# transceiver-AX5043.net
KiCad netlist of a schematic drawn in EAGLE
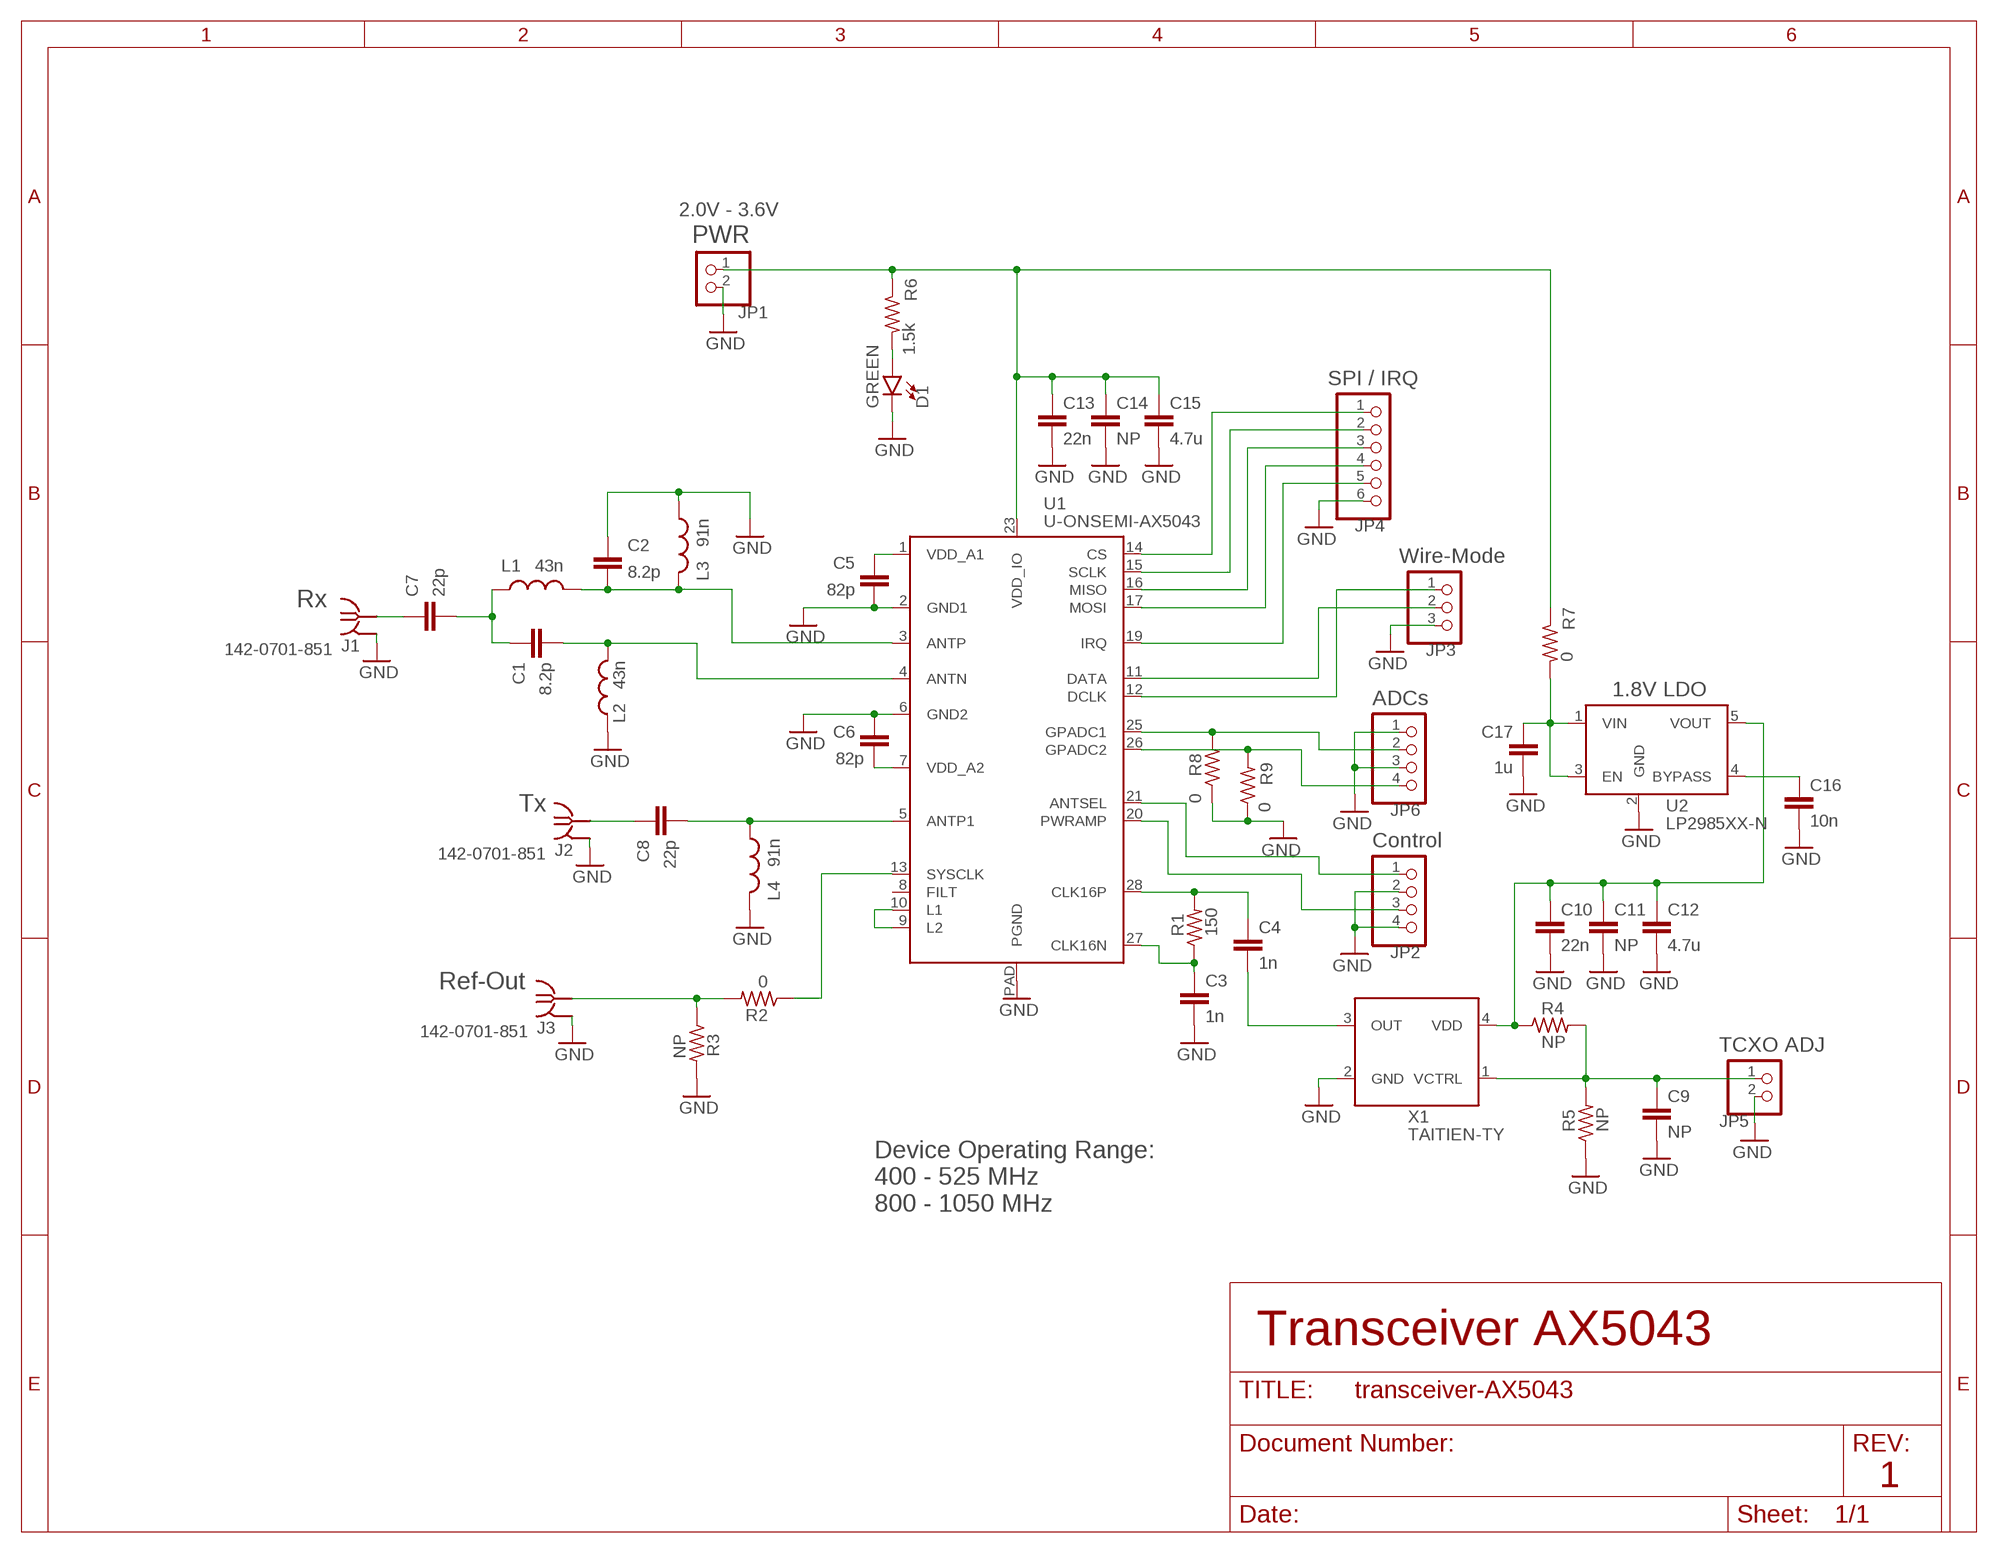
[diagram p0: schematic, sheet 1]

(export (version "E")
  (design (tool "Eeschema 10.0.6"))
  (components
    (comp (ref "C1")
      (value "8.2p")
      (footprint "eagle-import:.0402-C-NOSILK")
      (libsource (lib "eagle-import") (part "C-EU0402-C-NOSILK"))
    )
    (comp (ref "C2")
      (value "8.2p")
      (footprint "eagle-import:.0402-C-NOSILK")
      (libsource (lib "eagle-import") (part "C-EU0402-C-NOSILK"))
    )
    (comp (ref "C3")
      (value "1n")
      (footprint "eagle-import:.0402-C-NOSILK")
      (libsource (lib "eagle-import") (part "C-EU0402-C-NOSILK"))
    )
    (comp (ref "C4")
      (value "1n")
      (footprint "eagle-import:.0402-C-NOSILK")
      (libsource (lib "eagle-import") (part "C-EU0402-C-NOSILK"))
    )
    (comp (ref "C5")
      (value "82p")
      (footprint "eagle-import:.0402-C-NOSILK")
      (libsource (lib "eagle-import") (part "C-EU0402-C-NOSILK"))
    )
    (comp (ref "C6")
      (value "82p")
      (footprint "eagle-import:.0402-C-NOSILK")
      (libsource (lib "eagle-import") (part "C-EU0402-C-NOSILK"))
    )
    (comp (ref "C7")
      (value "22p")
      (footprint "eagle-import:.0402-C-NOSILK")
      (libsource (lib "eagle-import") (part "C-EU0402-C-NOSILK"))
    )
    (comp (ref "C8")
      (value "22p")
      (footprint "eagle-import:.0402-C-NOSILK")
      (libsource (lib "eagle-import") (part "C-EU0402-C-NOSILK"))
    )
    (comp (ref "C9")
      (value "NP")
      (footprint "eagle-import:.0603-C-NOSILK")
      (libsource (lib "eagle-import") (part "C-EU0603-C-NOSILK"))
    )
    (comp (ref "C10")
      (value "22n")
      (footprint "eagle-import:.0603-C-NOSILK")
      (libsource (lib "eagle-import") (part "C-EU0603-C-NOSILK"))
    )
    (comp (ref "C11")
      (value "NP")
      (footprint "eagle-import:.0603-C-NOSILK")
      (libsource (lib "eagle-import") (part "C-EU0603-C-NOSILK"))
    )
    (comp (ref "C12")
      (value "4.7u")
      (footprint "eagle-import:.0603-C-NOSILK")
      (libsource (lib "eagle-import") (part "C-EU0603-C-NOSILK"))
    )
    (comp (ref "C13")
      (value "22n")
      (footprint "eagle-import:.0603-C-NOSILK")
      (libsource (lib "eagle-import") (part "C-EU0603-C-NOSILK"))
    )
    (comp (ref "C14")
      (value "NP")
      (footprint "eagle-import:.0603-C-NOSILK")
      (libsource (lib "eagle-import") (part "C-EU0603-C-NOSILK"))
    )
    (comp (ref "C15")
      (value "4.7u")
      (footprint "eagle-import:.0603-C-NOSILK")
      (libsource (lib "eagle-import") (part "C-EU0603-C-NOSILK"))
    )
    (comp (ref "C16")
      (value "10n")
      (footprint "eagle-import:.0603-C-NOSILK")
      (libsource (lib "eagle-import") (part "C-EU0603-C-NOSILK"))
    )
    (comp (ref "C17")
      (value "1u")
      (footprint "eagle-import:.0603-C-NOSILK")
      (libsource (lib "eagle-import") (part "C-EU0603-C-NOSILK"))
    )
    (comp (ref "D1")
      (value "GREEN")
      (footprint "eagle-import:LED-0603")
      (libsource (lib "eagle-import") (part "LED-GREEN0603"))
    )
    (comp (ref "J1")
      (value "142-0701-851")
      (footprint "eagle-import:142-0701-851")
      (libsource (lib "eagle-import") (part "142-0701-851"))
    )
    (comp (ref "J2")
      (value "142-0701-851")
      (footprint "eagle-import:142-0701-851")
      (libsource (lib "eagle-import") (part "142-0701-851"))
    )
    (comp (ref "J3")
      (value "142-0701-851")
      (footprint "eagle-import:142-0701-851")
      (libsource (lib "eagle-import") (part "142-0701-851"))
    )
    (comp (ref "JP1")
      (value "PINHD-1X2")
      (footprint "eagle-import:1X02")
      (libsource (lib "eagle-import") (part "PINHD-1X2"))
    )
    (comp (ref "JP2")
      (value "PINHD-1X4")
      (footprint "eagle-import:1X04")
      (libsource (lib "eagle-import") (part "PINHD-1X4"))
    )
    (comp (ref "JP3")
      (value "PINHD-1X3")
      (footprint "eagle-import:1X03")
      (libsource (lib "eagle-import") (part "PINHD-1X3"))
    )
    (comp (ref "JP4")
      (value "PINHD-1X6")
      (footprint "eagle-import:1X06")
      (libsource (lib "eagle-import") (part "PINHD-1X6"))
    )
    (comp (ref "JP5")
      (value "PINHD-1X2")
      (footprint "eagle-import:1X02")
      (libsource (lib "eagle-import") (part "PINHD-1X2"))
    )
    (comp (ref "JP6")
      (value "PINHD-1X4")
      (footprint "eagle-import:1X04")
      (libsource (lib "eagle-import") (part "PINHD-1X4"))
    )
    (comp (ref "L1")
      (value "43n")
      (footprint "eagle-import:.0402-C-NOSILK")
      (libsource (lib "eagle-import") (part "L-US0402-C-NOSILK"))
    )
    (comp (ref "L2")
      (value "43n")
      (footprint "eagle-import:.0402-C-NOSILK")
      (libsource (lib "eagle-import") (part "L-US0402-C-NOSILK"))
    )
    (comp (ref "L3")
      (value "91n")
      (footprint "eagle-import:.0603-C-NOSILK")
      (libsource (lib "eagle-import") (part "L-US0603-C-NOSILK"))
    )
    (comp (ref "L4")
      (value "91n")
      (footprint "eagle-import:.0603-C-NOSILK")
      (libsource (lib "eagle-import") (part "L-US0603-C-NOSILK"))
    )
    (comp (ref "R1")
      (value "150")
      (footprint "eagle-import:.0402-C-NOSILK")
      (libsource (lib "eagle-import") (part "R-US_0402-C-NOSILK"))
    )
    (comp (ref "R2")
      (value "0")
      (footprint "eagle-import:.0402-C-NOSILK")
      (libsource (lib "eagle-import") (part "R-US_0402-C-NOSILK"))
    )
    (comp (ref "R3")
      (value "NP")
      (footprint "eagle-import:.0402-C-NOSILK")
      (libsource (lib "eagle-import") (part "R-US_0402-C-NOSILK"))
    )
    (comp (ref "R4")
      (value "NP")
      (footprint "eagle-import:.0603-B-NOSILK")
      (libsource (lib "eagle-import") (part "R-US_0603-B-NOSILK"))
    )
    (comp (ref "R5")
      (value "NP")
      (footprint "eagle-import:.0603-B-NOSILK")
      (libsource (lib "eagle-import") (part "R-US_0603-B-NOSILK"))
    )
    (comp (ref "R6")
      (value "1.5k")
      (footprint "eagle-import:.0603-B-NOSILK")
      (libsource (lib "eagle-import") (part "R-US_0603-B-NOSILK"))
    )
    (comp (ref "R7")
      (value "0")
      (footprint "eagle-import:.0603-C-NOSILK")
      (libsource (lib "eagle-import") (part "R-US_0603-C-NOSILK"))
    )
    (comp (ref "R8")
      (value "0")
      (footprint "eagle-import:.0402-C-NOSILK")
      (libsource (lib "eagle-import") (part "R-US_0402-C-NOSILK"))
    )
    (comp (ref "R9")
      (value "0")
      (footprint "eagle-import:.0402-C-NOSILK")
      (libsource (lib "eagle-import") (part "R-US_0402-C-NOSILK"))
    )
    (comp (ref "U1")
      (value "U-ONSEMI-AX5043")
      (footprint "eagle-import:QFN28-5X5-WITH-CENTER-PAD")
      (libsource (lib "eagle-import") (part "U-ONSEMI-AX5043"))
    )
    (comp (ref "U2")
      (value "LP2985XX-N")
      (footprint "eagle-import:SOT-23")
      (libsource (lib "eagle-import") (part "LP2985XX-N"))
    )
    (comp (ref "X1")
      (value "TAITIEN-TY")
      (footprint "eagle-import:2.5X2.0")
      (libsource (lib "eagle-import") (part "TAITIEN-TY"))
    )
  )
  (nets
    (net (code "1") (name "GND") (class "Default")
      (node (ref "C10") (pin "2") (pinfunction "2_2") (pintype "passive"))
      (node (ref "C11") (pin "2") (pinfunction "2_2") (pintype "passive"))
      (node (ref "C12") (pin "2") (pinfunction "2_2") (pintype "passive"))
      (node (ref "C13") (pin "2") (pinfunction "2_2") (pintype "passive"))
      (node (ref "C14") (pin "2") (pinfunction "2_2") (pintype "passive"))
      (node (ref "C15") (pin "2") (pinfunction "2_2") (pintype "passive"))
      (node (ref "C16") (pin "2") (pinfunction "2_2") (pintype "passive"))
      (node (ref "C17") (pin "2") (pinfunction "2_2") (pintype "passive"))
      (node (ref "C2") (pin "1") (pinfunction "1_1") (pintype "passive"))
      (node (ref "C3") (pin "2") (pinfunction "2_2") (pintype "passive"))
      (node (ref "C5") (pin "2") (pinfunction "2_2") (pintype "passive"))
      (node (ref "C6") (pin "1") (pinfunction "1_1") (pintype "passive"))
      (node (ref "C9") (pin "2") (pinfunction "2_2") (pintype "passive"))
      (node (ref "D1") (pin "C") (pinfunction "C_C") (pintype "passive"))
      (node (ref "J1") (pin "GND1") (pinfunction "GND_GND1") (pintype "bidirectional"))
      (node (ref "J1") (pin "GND2") (pinfunction "GND_GND2") (pintype "bidirectional"))
      (node (ref "J1") (pin "GND3") (pinfunction "GND_GND3") (pintype "bidirectional"))
      (node (ref "J1") (pin "GND4") (pinfunction "GND_GND4") (pintype "bidirectional"))
      (node (ref "J2") (pin "GND1") (pinfunction "GND_GND1") (pintype "bidirectional"))
      (node (ref "J2") (pin "GND2") (pinfunction "GND_GND2") (pintype "bidirectional"))
      (node (ref "J2") (pin "GND3") (pinfunction "GND_GND3") (pintype "bidirectional"))
      (node (ref "J2") (pin "GND4") (pinfunction "GND_GND4") (pintype "bidirectional"))
      (node (ref "J3") (pin "GND1") (pinfunction "GND_GND1") (pintype "bidirectional"))
      (node (ref "J3") (pin "GND2") (pinfunction "GND_GND2") (pintype "bidirectional"))
      (node (ref "J3") (pin "GND3") (pinfunction "GND_GND3") (pintype "bidirectional"))
      (node (ref "J3") (pin "GND4") (pinfunction "GND_GND4") (pintype "bidirectional"))
      (node (ref "JP1") (pin "2") (pinfunction "2_2") (pintype "passive"))
      (node (ref "JP2") (pin "2") (pinfunction "2_2") (pintype "passive"))
      (node (ref "JP2") (pin "4") (pinfunction "4_4") (pintype "passive"))
      (node (ref "JP3") (pin "3") (pinfunction "3_3") (pintype "passive"))
      (node (ref "JP4") (pin "6") (pinfunction "6_6") (pintype "passive"))
      (node (ref "JP5") (pin "2") (pinfunction "2_2") (pintype "passive"))
      (node (ref "JP6") (pin "1") (pinfunction "1_1") (pintype "passive"))
      (node (ref "JP6") (pin "3") (pinfunction "3_3") (pintype "passive"))
      (node (ref "L2") (pin "1") (pinfunction "1_1") (pintype "passive"))
      (node (ref "L3") (pin "2") (pinfunction "2_2") (pintype "passive"))
      (node (ref "L4") (pin "1") (pinfunction "1_1") (pintype "passive"))
      (node (ref "R3") (pin "2") (pinfunction "2_2") (pintype "passive"))
      (node (ref "R5") (pin "1") (pinfunction "1_1") (pintype "passive"))
      (node (ref "R8") (pin "1") (pinfunction "1_1") (pintype "passive"))
      (node (ref "R9") (pin "1") (pinfunction "1_1") (pintype "passive"))
      (node (ref "U1") (pin "2") (pinfunction "GND1_2") (pintype "power_in"))
      (node (ref "U1") (pin "6") (pinfunction "GND2_6") (pintype "power_in"))
      (node (ref "U1") (pin "PAD") (pinfunction "PGND_PAD") (pintype "power_in"))
      (node (ref "U2") (pin "2") (pinfunction "GND_2") (pintype "power_in"))
      (node (ref "X1") (pin "2") (pinfunction "GND_2") (pintype "power_in"))
    )
    (net (code "2") (name "Net-(C1-Pad1)") (class "Default")
      (node (ref "C1") (pin "1") (pinfunction "1_1") (pintype "passive"))
      (node (ref "C7") (pin "2") (pinfunction "2_2") (pintype "passive"))
      (node (ref "L1") (pin "1") (pinfunction "1_1") (pintype "passive"))
    )
    (net (code "3") (name "Net-(D1-PadA)") (class "Default")
      (node (ref "D1") (pin "A") (pinfunction "A_A") (pintype "passive"))
      (node (ref "R6") (pin "2") (pinfunction "2_2") (pintype "passive"))
    )
    (net (code "4") (name "Net-(J1-RF)") (class "Default")
      (node (ref "C7") (pin "1") (pinfunction "1_1") (pintype "passive"))
      (node (ref "J1") (pin "RF1") (pinfunction "RF_RF1") (pintype "bidirectional"))
    )
    (net (code "5") (name "Net-(J2-RF)") (class "Default")
      (node (ref "C8") (pin "1") (pinfunction "1_1") (pintype "passive"))
      (node (ref "J2") (pin "RF1") (pinfunction "RF_RF1") (pintype "bidirectional"))
    )
    (net (code "6") (name "Net-(J3-RF)") (class "Default")
      (node (ref "J3") (pin "RF1") (pinfunction "RF_RF1") (pintype "bidirectional"))
      (node (ref "R2") (pin "2") (pinfunction "2_2") (pintype "passive"))
      (node (ref "R3") (pin "1") (pinfunction "1_1") (pintype "passive"))
    )
    (net (code "7") (name "Net-(U1-ANTN)") (class "Default")
      (node (ref "C1") (pin "2") (pinfunction "2_2") (pintype "passive"))
      (node (ref "L2") (pin "2") (pinfunction "2_2") (pintype "passive"))
      (node (ref "U1") (pin "4") (pinfunction "ANTN_4") (pintype "bidirectional"))
    )
    (net (code "8") (name "Net-(U1-ANTP)") (class "Default")
      (node (ref "C2") (pin "2") (pinfunction "2_2") (pintype "passive"))
      (node (ref "L1") (pin "2") (pinfunction "2_2") (pintype "passive"))
      (node (ref "L3") (pin "1") (pinfunction "1_1") (pintype "passive"))
      (node (ref "U1") (pin "3") (pinfunction "ANTP_3") (pintype "bidirectional"))
    )
    (net (code "9") (name "Net-(U1-ANTP1)") (class "Default")
      (node (ref "C8") (pin "2") (pinfunction "2_2") (pintype "passive"))
      (node (ref "L4") (pin "2") (pinfunction "2_2") (pintype "passive"))
      (node (ref "U1") (pin "5") (pinfunction "ANTP1_5") (pintype "bidirectional"))
    )
    (net (code "10") (name "Net-(U1-ANTSEL)") (class "Default")
      (node (ref "JP2") (pin "1") (pinfunction "1_1") (pintype "passive"))
      (node (ref "U1") (pin "21") (pinfunction "ANTSEL_21") (pintype "bidirectional"))
    )
    (net (code "11") (name "Net-(U1-CLK16N)") (class "Default")
      (node (ref "C3") (pin "1") (pinfunction "1_1") (pintype "passive"))
      (node (ref "R1") (pin "1") (pinfunction "1_1") (pintype "passive"))
      (node (ref "U1") (pin "27") (pinfunction "CLK16N_27") (pintype "passive"))
    )
    (net (code "12") (name "Net-(U1-CLK16P)") (class "Default")
      (node (ref "C4") (pin "1") (pinfunction "1_1") (pintype "passive"))
      (node (ref "R1") (pin "2") (pinfunction "2_2") (pintype "passive"))
      (node (ref "U1") (pin "28") (pinfunction "CLK16P_28") (pintype "passive"))
    )
    (net (code "13") (name "Net-(U1-CS)") (class "Default")
      (node (ref "JP4") (pin "1") (pinfunction "1_1") (pintype "passive"))
      (node (ref "U1") (pin "14") (pinfunction "CS_14") (pintype "input"))
    )
    (net (code "14") (name "Net-(U1-DATA)") (class "Default")
      (node (ref "JP3") (pin "2") (pinfunction "2_2") (pintype "passive"))
      (node (ref "U1") (pin "11") (pinfunction "DATA_11") (pintype "bidirectional"))
    )
    (net (code "15") (name "Net-(U1-DCLK)") (class "Default")
      (node (ref "JP3") (pin "1") (pinfunction "1_1") (pintype "passive"))
      (node (ref "U1") (pin "12") (pinfunction "DCLK_12") (pintype "bidirectional"))
    )
    (net (code "16") (name "Net-(U1-GPADC1)") (class "Default")
      (node (ref "JP6") (pin "2") (pinfunction "2_2") (pintype "passive"))
      (node (ref "R8") (pin "2") (pinfunction "2_2") (pintype "passive"))
      (node (ref "U1") (pin "25") (pinfunction "GPADC1_25") (pintype "input"))
    )
    (net (code "17") (name "Net-(U1-GPADC2)") (class "Default")
      (node (ref "JP6") (pin "4") (pinfunction "4_4") (pintype "passive"))
      (node (ref "R9") (pin "2") (pinfunction "2_2") (pintype "passive"))
      (node (ref "U1") (pin "26") (pinfunction "GPADC2_26") (pintype "input"))
    )
    (net (code "18") (name "Net-(U1-IRQ)") (class "Default")
      (node (ref "JP4") (pin "5") (pinfunction "5_5") (pintype "passive"))
      (node (ref "U1") (pin "19") (pinfunction "IRQ_19") (pintype "bidirectional"))
    )
    (net (code "19") (name "Net-(U1-L1)") (class "Default")
      (node (ref "U1") (pin "10") (pinfunction "L1_10") (pintype "input"))
      (node (ref "U1") (pin "9") (pinfunction "L2_9") (pintype "input"))
    )
    (net (code "20") (name "Net-(U1-MISO)") (class "Default")
      (node (ref "JP4") (pin "3") (pinfunction "3_3") (pintype "passive"))
      (node (ref "U1") (pin "16") (pinfunction "MISO_16") (pintype "output"))
    )
    (net (code "21") (name "Net-(U1-MOSI)") (class "Default")
      (node (ref "JP4") (pin "4") (pinfunction "4_4") (pintype "passive"))
      (node (ref "U1") (pin "17") (pinfunction "MOSI_17") (pintype "input"))
    )
    (net (code "22") (name "Net-(U1-PWRAMP)") (class "Default")
      (node (ref "JP2") (pin "3") (pinfunction "3_3") (pintype "passive"))
      (node (ref "U1") (pin "20") (pinfunction "PWRAMP_20") (pintype "bidirectional"))
    )
    (net (code "23") (name "Net-(U1-SCLK)") (class "Default")
      (node (ref "JP4") (pin "2") (pinfunction "2_2") (pintype "passive"))
      (node (ref "U1") (pin "15") (pinfunction "SCLK_15") (pintype "input"))
    )
    (net (code "24") (name "Net-(U1-SYSCLK)") (class "Default")
      (node (ref "R2") (pin "1") (pinfunction "1_1") (pintype "passive"))
      (node (ref "U1") (pin "13") (pinfunction "SYSCLK_13") (pintype "bidirectional"))
    )
    (net (code "25") (name "Net-(U1-VDD_A1)") (class "Default")
      (node (ref "C5") (pin "1") (pinfunction "1_1") (pintype "passive"))
      (node (ref "U1") (pin "1") (pinfunction "VDD_A1_1") (pintype "power_in"))
    )
    (net (code "26") (name "Net-(U1-VDD_A2)") (class "Default")
      (node (ref "C6") (pin "2") (pinfunction "2_2") (pintype "passive"))
      (node (ref "U1") (pin "7") (pinfunction "VDD_A2_7") (pintype "power_in"))
    )
    (net (code "27") (name "Net-(U1-VDD_IO)") (class "Default")
      (node (ref "C13") (pin "1") (pinfunction "1_1") (pintype "passive"))
      (node (ref "C14") (pin "1") (pinfunction "1_1") (pintype "passive"))
      (node (ref "C15") (pin "1") (pinfunction "1_1") (pintype "passive"))
      (node (ref "JP1") (pin "1") (pinfunction "1_1") (pintype "passive"))
      (node (ref "R6") (pin "1") (pinfunction "1_1") (pintype "passive"))
      (node (ref "R7") (pin "1") (pinfunction "1_1") (pintype "passive"))
      (node (ref "U1") (pin "23") (pinfunction "VDD_IO_23") (pintype "power_in"))
    )
    (net (code "28") (name "Net-(U2-BYPASS)") (class "Default")
      (node (ref "C16") (pin "1") (pinfunction "1_1") (pintype "passive"))
      (node (ref "U2") (pin "4") (pinfunction "BYPASS_4") (pintype "power_in"))
    )
    (net (code "29") (name "Net-(U2-EN)") (class "Default")
      (node (ref "C17") (pin "1") (pinfunction "1_1") (pintype "passive"))
      (node (ref "R7") (pin "2") (pinfunction "2_2") (pintype "passive"))
      (node (ref "U2") (pin "1") (pinfunction "VIN_1") (pintype "power_in"))
      (node (ref "U2") (pin "3") (pinfunction "EN_3") (pintype "input"))
    )
    (net (code "30") (name "Net-(U2-VOUT)") (class "Default")
      (node (ref "C10") (pin "1") (pinfunction "1_1") (pintype "passive"))
      (node (ref "C11") (pin "1") (pinfunction "1_1") (pintype "passive"))
      (node (ref "C12") (pin "1") (pinfunction "1_1") (pintype "passive"))
      (node (ref "R4") (pin "1") (pinfunction "1_1") (pintype "passive"))
      (node (ref "U2") (pin "5") (pinfunction "VOUT_5") (pintype "power_in"))
      (node (ref "X1") (pin "4") (pinfunction "VDD_4") (pintype "power_in"))
    )
    (net (code "31") (name "Net-(X1-OUT)") (class "Default")
      (node (ref "C4") (pin "2") (pinfunction "2_2") (pintype "passive"))
      (node (ref "X1") (pin "3") (pinfunction "OUT_3") (pintype "output"))
    )
    (net (code "32") (name "Net-(X1-VCTRL)") (class "Default")
      (node (ref "C9") (pin "1") (pinfunction "1_1") (pintype "passive"))
      (node (ref "JP5") (pin "1") (pinfunction "1_1") (pintype "passive"))
      (node (ref "R4") (pin "2") (pinfunction "2_2") (pintype "passive"))
      (node (ref "R5") (pin "2") (pinfunction "2_2") (pintype "passive"))
      (node (ref "X1") (pin "1") (pinfunction "VCTRL_1") (pintype "input"))
    )
    (net (code "33") (name "unconnected-(U1-FILT-Pad8)") (class "Default")
      (node (ref "U1") (pin "8") (pinfunction "FILT_8") (pintype "output"))
    )
  )
)
